# Buck5.net
KiCad netlist of a schematic drawn in Altium Designer
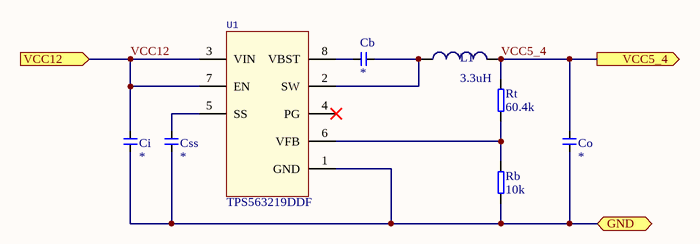
[diagram p0: Buck5.SchDoc]

(export (version "E")
  (design (tool "Eeschema 10.0.6"))
  (components
    (comp (ref "Cb")
      (value "*")
      (footprint "Controller:CAP 0603/1608")
      (description "Capacitor")
      (libsource (lib "Controller") (part "CAP"))
    )
    (comp (ref "Ci")
      (value "*")
      (footprint "Controller:CAP 0603/1608")
      (description "Capacitor")
      (libsource (lib "Controller") (part "CAP"))
    )
    (comp (ref "Co")
      (value "*")
      (footprint "Controller:CAP 0603/1608")
      (description "Capacitor")
      (libsource (lib "Controller") (part "CAP"))
    )
    (comp (ref "Css")
      (value "*")
      (footprint "Controller:CAP 0603/1608")
      (description "Capacitor")
      (libsource (lib "Controller") (part "CAP"))
    )
    (comp (ref "L1")
      (value "3.3uH")
      (footprint "Controller:INDUCTOR PCC-M0530M3R3KVP")
      (description "Inductor")
      (fields (field (name "PUBLISHER") "Altium Limited"))
      (libsource (lib "Controller") (part "Inductor"))
    )
    (comp (ref "Rb")
      (value "10k")
      (footprint "Controller:RES 0603/1608")
      (description "Resistor")
      (libsource (lib "Controller") (part "RES"))
    )
    (comp (ref "Rt")
      (value "60.4k")
      (footprint "Controller:RES 0603/1608")
      (description "Resistor")
      (libsource (lib "Controller") (part "RES"))
    )
    (comp (ref "U1")
      (value "TPS563219DDF")
      (footprint "Controller:TSOP65P280X110-8N")
      (libsource (lib "Controller") (part "TPS563219DDF"))
    )
  )
  (nets
    (net (code "1") (name "/GND") (class "Default")
      (node (ref "Ci") (pin "2") (pinfunction "2_2") (pintype "passive"))
      (node (ref "Co") (pin "2") (pinfunction "2_2") (pintype "passive"))
      (node (ref "Css") (pin "2") (pinfunction "2_2") (pintype "passive"))
      (node (ref "Rb") (pin "1") (pinfunction "1_1") (pintype "passive"))
      (node (ref "U1") (pin "1") (pinfunction "GND_1") (pintype "power_in"))
    )
    (net (code "2") (name "/VCC5_4") (class "Default")
      (node (ref "Co") (pin "1") (pinfunction "1_1") (pintype "passive"))
      (node (ref "L1") (pin "2") (pinfunction "2_2") (pintype "passive"))
      (node (ref "Rt") (pin "2") (pinfunction "2_2") (pintype "passive"))
    )
    (net (code "3") (name "/VCC12") (class "Default")
      (node (ref "Ci") (pin "1") (pinfunction "1_1") (pintype "passive"))
      (node (ref "U1") (pin "3") (pinfunction "VIN_3") (pintype "power_in"))
      (node (ref "U1") (pin "7") (pinfunction "EN_7") (pintype "power_in"))
    )
    (net (code "4") (name "Net-(U1-SS)") (class "Default")
      (node (ref "Css") (pin "1") (pinfunction "1_1") (pintype "passive"))
      (node (ref "U1") (pin "5") (pinfunction "SS_5") (pintype "power_in"))
    )
    (net (code "5") (name "Net-(U1-SW)") (class "Default")
      (node (ref "Cb") (pin "1") (pinfunction "1_1") (pintype "passive"))
      (node (ref "L1") (pin "1") (pinfunction "1_1") (pintype "passive"))
      (node (ref "U1") (pin "2") (pinfunction "SW_2") (pintype "power_in"))
    )
    (net (code "6") (name "Net-(U1-VBST)") (class "Default")
      (node (ref "Cb") (pin "2") (pinfunction "2_2") (pintype "passive"))
      (node (ref "U1") (pin "8") (pinfunction "VBST_8") (pintype "power_in"))
    )
    (net (code "7") (name "Net-(U1-VFB)") (class "Default")
      (node (ref "Rb") (pin "2") (pinfunction "2_2") (pintype "passive"))
      (node (ref "Rt") (pin "1") (pinfunction "1_1") (pintype "passive"))
      (node (ref "U1") (pin "6") (pinfunction "VFB_6") (pintype "power_in"))
    )
    (net (code "8") (name "unconnected-(U1-PG-Pad4)") (class "Default")
      (node (ref "U1") (pin "4") (pinfunction "PG_4") (pintype "power_in+no_connect"))
    )
  )
)
